# Power.net
KiCad netlist of a schematic drawn in Altium Designer
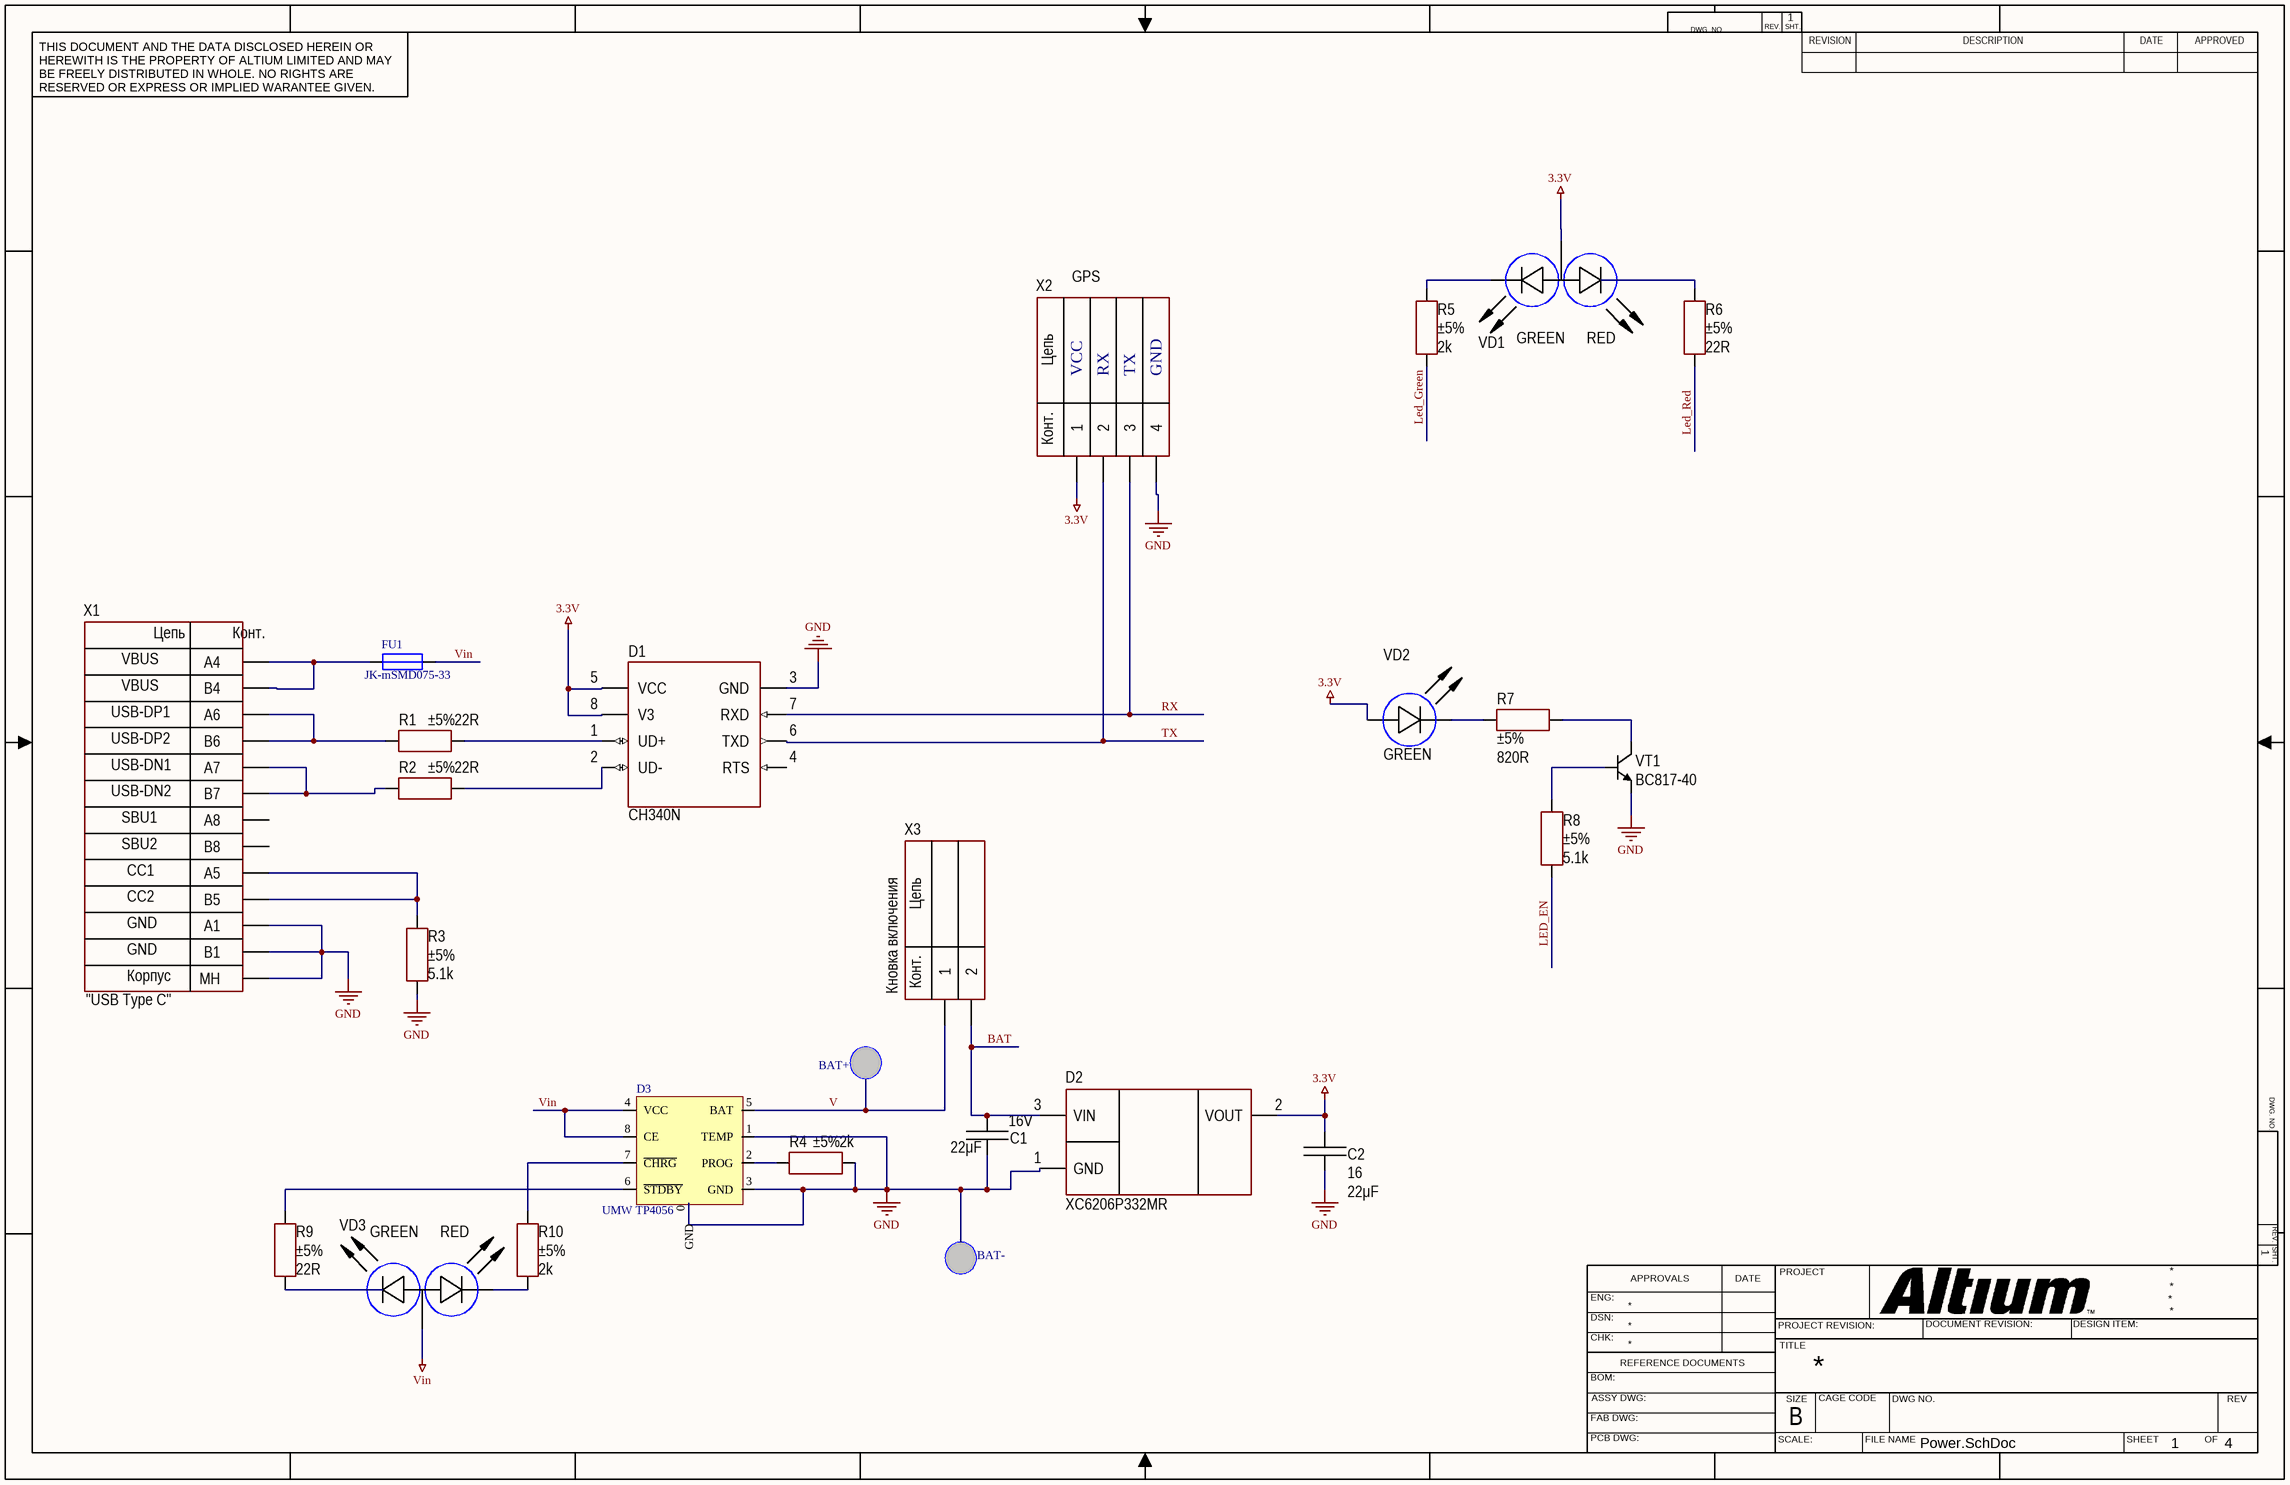
[diagram p0: Power.SchDoc]

(export (version "E")
  (design (tool "Eeschema 10.0.6"))
  (components
    (comp (ref "C1")
      (value "22μF")
      (footprint "standard-case:CAP: 1206")
      (fields
        (field (name "MANUFACTURER") "Yageo")
        (field (name "VALUEMANUFACTURERPARTNUMBER") "Ceramic capacitor, 22μF, X5R, ±20%, 16V, 1206, -55...+125°C")
        (field (name "TOLERANCE") "±20%")
        (field (name "VOLTAGE") "16V")
      )
      (libsource (lib "capacitor") (part "Ceramic_1206"))
    )
    (comp (ref "C2")
      (value "22μF")
      (footprint "standard-case:CAP: 1206")
      (fields
        (field (name "MANUFACTURER") "Yageo")
        (field (name "VALUEMANUFACTURERPARTNUMBER") "Ceramic capacitor, 22μF, X5R, ±20%, 16, 1206, -55...+125°C")
        (field (name "TOLERANCE") "±20%")
        (field (name "VOLTAGE") "16")
      )
      (libsource (lib "capacitor") (part "Ceramic_1206"))
    )
    (comp (ref "D1")
      (value "~")
      (footprint "8-SOIC")
      (description "USB-to-UART")
      (fields
        (field (name "MANUFACTURER") "WCH(Jiangsu Qin Heng)")
        (field (name "VALUEMANUFACTURERPARTNUMBER") "IC usb-to-uart bridge, USB2.0, 3...3.6V, -40...+85°C, 8- SOP")
        (field (name "PARTNUMBER") "CH340N")
      )
      (libsource (lib "ic-interface") (part "CH340N"))
    )
    (comp (ref "D2")
      (value "~")
      (footprint "SOT23")
      (description "Linear voltage regulator")
      (fields
        (field (name "MANUFACTURER") "Torex")
        (field (name "VALUEMANUFACTURERPARTNUMBER") "Linear voltage regulator, max input 6V, 0.25V, output 3.3V, 200mA, -40...+85°C, SOT-23")
        (field (name "PARTNUMBER") "XC6206P332MR")
      )
      (libsource (lib "ic-power-supply") (part "XC6206"))
    )
    (comp (ref "D3")
      (value "UMW TP4056")
      (footprint "SOP-8")
      (description "Микросхема TP4056-42-ESOP8")
      (libsource (lib "Geksan_my") (part "D TP4056-42-ESOP8"))
    )
    (comp (ref "FU1")
      (value "JK-mSMD075-33")
      (footprint "FUSE: 1812")
      (description "Предохраниетель ток срабатывания 1,5А, ток удержания 750мА")
      (libsource (lib "Fuse") (part "JK-mSMD075-33"))
    )
    (comp (ref "R1")
      (value "22R")
      (footprint "standard-case:RES: 0805")
      (fields
        (field (name "MANUFACTURER") "Yageo")
        (field (name "PARTNUMBER") "RC0805JR-0722RL")
        (field (name "VALUEMANUFACTURERPARTNUMBER") "Resistor film, 22R, ±5%, 0805, 0.125W, -55...+125°C")
        (field (name "TOLERANCE") "±5%")
      )
      (libsource (lib "") (part "Resistor_0805_1"))
    )
    (comp (ref "R2")
      (value "22R")
      (footprint "standard-case:RES: 0805")
      (fields
        (field (name "MANUFACTURER") "Yageo")
        (field (name "PARTNUMBER") "RC0805JR-0722RL")
        (field (name "VALUEMANUFACTURERPARTNUMBER") "Resistor film, 22R, ±5%, 0805, 0.125W, -55...+125°C")
        (field (name "TOLERANCE") "±5%")
      )
      (libsource (lib "") (part "Resistor_0805_1"))
    )
    (comp (ref "R3")
      (value "5.1k")
      (footprint "standard-case:RES: 0805")
      (fields
        (field (name "MANUFACTURER") "Yageo")
        (field (name "PARTNUMBER") "RC0805JR-075K1L")
        (field (name "VALUEMANUFACTURERPARTNUMBER") "Resistor film, 5.1k, ±5%, 0805, 0.125W, -55...+125°C")
        (field (name "TOLERANCE") "±5%")
      )
      (libsource (lib "resistor") (part "Resistor_0805"))
    )
    (comp (ref "R4")
      (value "2k")
      (footprint "standard-case:RES: 0805")
      (fields
        (field (name "MANUFACTURER") "Yageo")
        (field (name "PARTNUMBER") "RC0805JR-0712KL")
        (field (name "VALUEMANUFACTURERPARTNUMBER") "Resistor film, 2k, ±5%, 0805, 0.125W, -55...+125°C")
        (field (name "TOLERANCE") "±5%")
      )
      (libsource (lib "") (part "Resistor_0805_1"))
    )
    (comp (ref "R5")
      (value "2k")
      (footprint "standard-case:RES: 0805")
      (fields
        (field (name "MANUFACTURER") "Yageo")
        (field (name "PARTNUMBER") "RC0805JR-0712KL")
        (field (name "VALUEMANUFACTURERPARTNUMBER") "Resistor film, 2k, ±5%, 0805, 0.125W, -55...+125°C")
        (field (name "TOLERANCE") "±5%")
      )
      (libsource (lib "") (part "Resistor_0805_2"))
    )
    (comp (ref "R6")
      (value "22R")
      (footprint "standard-case:RES: 0805")
      (fields
        (field (name "MANUFACTURER") "Yageo")
        (field (name "PARTNUMBER") "RC0805JR-0722RL")
        (field (name "VALUEMANUFACTURERPARTNUMBER") "Resistor film, 22R, ±5%, 0805, 0.125W, -55...+125°C")
        (field (name "TOLERANCE") "±5%")
      )
      (libsource (lib "") (part "Resistor_0805_2"))
    )
    (comp (ref "R7")
      (value "820R")
      (footprint "standard-case:RES: 0805")
      (fields
        (field (name "MANUFACTURER") "Yageo")
        (field (name "PARTNUMBER") "RC0805JR-07820RL")
        (field (name "VALUEMANUFACTURERPARTNUMBER") "Resistor film, 820R, ±5%, 0805, 0.125W, -55...+125°C")
        (field (name "TOLERANCE") "±5%")
      )
      (libsource (lib "") (part "Resistor_0805_1"))
    )
    (comp (ref "R8")
      (value "5.1k")
      (footprint "standard-case:RES: 0805")
      (fields
        (field (name "MANUFACTURER") "Yageo")
        (field (name "PARTNUMBER") "RC0805JR-075K1L")
        (field (name "VALUEMANUFACTURERPARTNUMBER") "Resistor film, 5.1k, ±5%, 0805, 0.125W, -55...+125°C")
        (field (name "TOLERANCE") "±5%")
      )
      (libsource (lib "") (part "Resistor_0805_2"))
    )
    (comp (ref "R9")
      (value "22R")
      (footprint "standard-case:RES: 0805")
      (fields
        (field (name "MANUFACTURER") "Yageo")
        (field (name "PARTNUMBER") "RC0805JR-0722RL")
        (field (name "VALUEMANUFACTURERPARTNUMBER") "Resistor film, 22R, ±5%, 0805, 0.125W, -55...+125°C")
        (field (name "TOLERANCE") "±5%")
      )
      (libsource (lib "resistor") (part "Resistor_0805"))
    )
    (comp (ref "R10")
      (value "2k")
      (footprint "standard-case:RES: 0805")
      (fields
        (field (name "MANUFACTURER") "Yageo")
        (field (name "PARTNUMBER") "RC0805JR-0712KL")
        (field (name "VALUEMANUFACTURERPARTNUMBER") "Resistor film, 2k, ±5%, 0805, 0.125W, -55...+125°C")
        (field (name "TOLERANCE") "±5%")
      )
      (libsource (lib "resistor") (part "Resistor_0805"))
    )
    (comp (ref "VD1")
      (value "~")
      (footprint "DIODE: LED3MM_DUAL")
      (fields
        (field (name "VALUEMANUFACTURERPARTNUMBER") "LED, Green, *, *, 3mm, -55...+150°C")
        (field (name "COLOR") "GREEN      RED")
      )
      (libsource (lib "diode") (part "LED_DUAL_3mm"))
    )
    (comp (ref "VD2")
      (value "~")
      (footprint "DIODE: LED3MM_Y")
      (fields
        (field (name "VALUEMANUFACTURERPARTNUMBER") "LED, Green, *, *, *, -55...+150°C")
        (field (name "COLOR") "GREEN")
      )
      (libsource (lib "diode") (part "LED_single_3mm"))
    )
    (comp (ref "VD3")
      (value "~")
      (footprint "DIODE: LED3MM_DUAL")
      (fields
        (field (name "VALUEMANUFACTURERPARTNUMBER") "LED, Green, *, *, 3mm, -55...+150°C")
        (field (name "COLOR") "GREEN      RED")
      )
      (libsource (lib "diode") (part "LED_DUAL_3mm"))
    )
    (comp (ref "VT1")
      (value "~")
      (footprint "standard-case:SOT23")
      (fields
        (field (name "MANUFACTURER") "ON Semiconductor")
        (field (name "VALUEMANUFACTURERPARTNUMBER") "NPN transistor, 45V, 100mA, 100MHz, 250mW, 0.6V, 420, SOT-23, -55...+125°C")
        (field (name "PARTNUMBER") "ВС817-40")
      )
      (libsource (lib "transistor") (part "BJT_NPN_132"))
    )
    (comp (ref "X1")
      (value "~")
      (footprint "custom-case:CON: TYPE-C-31-M-12")
      (fields
        (field (name "MANUFACTURER") "Korean Hroparts")
        (field (name "VALUEMANUFACTURERPARTNUMBER") "USB Type C, 3A")
        (field (name "PARTNUMBER") "TYPE-C-31-M-12")
        (field (name "COMMENTTEXT") "\"USB Type C\"")
      )
      (libsource (lib "connector") (part "Connector_USB_Type_C"))
    )
    (comp (ref "X2")
      (value "~")
      (footprint "custom-case:CON: PLS-4")
      (fields
        (field (name "MANUFACTURER") "Connfly")
        (field (name "VALUEMANUFACTURERPARTNUMBER") "Connector, 4pin, 2.54mm, 500VAC, 3A")
        (field (name "PARTNUMBER") "PLS-4")
        (field (name "COMMENTTEXT") "GPS")
      )
      (libsource (lib "connector") (part "PLS-4"))
    )
    (comp (ref "X3")
      (value "~")
      (footprint "custom-case:CON: PLS-2")
      (fields
        (field (name "MANUFACTURER") "Connfly")
        (field (name "VALUEMANUFACTURERPARTNUMBER") "Connector, 2pin, 2.54mm, 500VAC, 3A")
        (field (name "PARTNUMBER") "PLS-2")
        (field (name "COMMENTTEXT") "Кновка включения")
      )
      (libsource (lib "connector") (part "PLS-2"))
    )
  )
  (nets
    (net (code "1") (name "/BAT") (class "Default")
      (node (ref "C1") (pin "2") (pinfunction "2_2") (pintype "passive"))
      (node (ref "D2") (pin "3") (pinfunction "VIN_3") (pintype "power_in"))
      (node (ref "X3") (pin "2") (pinfunction "2_2") (pintype "passive"))
    )
    (net (code "2") (name "/LED_EN") (class "Default")
      (node (ref "R8") (pin "2") (pinfunction "2_2") (pintype "passive"))
    )
    (net (code "3") (name "/Led_Green") (class "Default")
      (node (ref "R5") (pin "2") (pinfunction "2_2") (pintype "passive"))
    )
    (net (code "4") (name "/Led_Red") (class "Default")
      (node (ref "R6") (pin "2") (pinfunction "2_2") (pintype "passive"))
    )
    (net (code "5") (name "/RX") (class "Default")
      (node (ref "D1") (pin "7") (pinfunction "RXD_7") (pintype "input"))
      (node (ref "X2") (pin "3") (pinfunction "3_3") (pintype "power_in"))
    )
    (net (code "6") (name "/TX") (class "Default")
      (node (ref "D1") (pin "6") (pinfunction "TXD_6") (pintype "output"))
      (node (ref "X2") (pin "2") (pinfunction "2_2") (pintype "passive"))
    )
    (net (code "7") (name "/V") (class "Default")
      (node (ref "D3") (pin "5") (pinfunction "BAT_5") (pintype "open_collector"))
      (node (ref "X3") (pin "1") (pinfunction "1_1") (pintype "passive"))
    )
    (net (code "8") (name "3.3V") (class "Default")
      (node (ref "C2") (pin "2") (pinfunction "2_2") (pintype "passive"))
      (node (ref "D1") (pin "5") (pinfunction "VCC_5") (pintype "power_in"))
      (node (ref "D1") (pin "8") (pinfunction "V3_8") (pintype "passive"))
      (node (ref "D2") (pin "2") (pinfunction "VOUT_2") (pintype "power_in"))
      (node (ref "VD1") (pin "2") (pinfunction "A_2") (pintype "passive"))
      (node (ref "VD2") (pin "1") (pinfunction "A_1") (pintype "passive"))
      (node (ref "X2") (pin "1") (pinfunction "1_1") (pintype "passive"))
    )
    (net (code "9") (name "GND") (class "Default")
      (node (ref "C1") (pin "1") (pinfunction "1_1") (pintype "passive"))
      (node (ref "C2") (pin "1") (pinfunction "1_1") (pintype "passive"))
      (node (ref "D1") (pin "3") (pinfunction "GND_3") (pintype "power_in"))
      (node (ref "D2") (pin "1") (pinfunction "GND_1") (pintype "power_in"))
      (node (ref "D3") (pin "0") (pinfunction "GND_0") (pintype "power_in"))
      (node (ref "D3") (pin "1") (pinfunction "TEMP_1") (pintype "power_in"))
      (node (ref "D3") (pin "3") (pinfunction "GND_3") (pintype "power_in"))
      (node (ref "R3") (pin "1") (pinfunction "1_1") (pintype "passive"))
      (node (ref "R4") (pin "2") (pinfunction "2_2") (pintype "passive"))
      (node (ref "VT1") (pin "2") (pinfunction "E_2") (pintype "passive"))
      (node (ref "X1") (pin "A1") (pinfunction "A1_A1") (pintype "power_in"))
      (node (ref "X1") (pin "B1") (pinfunction "B1_B1") (pintype "power_in"))
      (node (ref "X1") (pin "MH") (pinfunction "MH_MH") (pintype "power_in"))
      (node (ref "X2") (pin "4") (pinfunction "4_4") (pintype "power_in"))
    )
    (net (code "10") (name "Net-(D1-UD+)") (class "Default")
      (node (ref "D1") (pin "1") (pinfunction "UD+_1") (pintype "bidirectional"))
      (node (ref "R1") (pin "2") (pinfunction "2_2") (pintype "passive"))
    )
    (net (code "11") (name "Net-(D1-UD-)") (class "Default")
      (node (ref "D1") (pin "2") (pinfunction "UD-_2") (pintype "bidirectional"))
      (node (ref "R2") (pin "2") (pinfunction "2_2") (pintype "passive"))
    )
    (net (code "12") (name "Net-(D3-PROG)") (class "Default")
      (node (ref "D3") (pin "2") (pinfunction "PROG_2") (pintype "power_in"))
      (node (ref "R4") (pin "1") (pinfunction "1_1") (pintype "passive"))
    )
    (net (code "13") (name "Net-(D3-~{CHRG})") (class "Default")
      (node (ref "D3") (pin "7") (pinfunction "~{CHRG}_7") (pintype "open_collector"))
      (node (ref "R10") (pin "2") (pinfunction "2_2") (pintype "passive"))
    )
    (net (code "14") (name "Net-(D3-~{STDBY})") (class "Default")
      (node (ref "D3") (pin "6") (pinfunction "~{STDBY}_6") (pintype "passive"))
      (node (ref "R9") (pin "2") (pinfunction "2_2") (pintype "passive"))
    )
    (net (code "15") (name "Net-(FU1-Pad1)") (class "Default")
      (node (ref "FU1") (pin "1") (pinfunction "1_1") (pintype "passive"))
      (node (ref "X1") (pin "A4") (pinfunction "A4_A4") (pintype "passive"))
      (node (ref "X1") (pin "B4") (pinfunction "B4_B4") (pintype "passive"))
    )
    (net (code "16") (name "Net-(R1-Pad1)") (class "Default")
      (node (ref "R1") (pin "1") (pinfunction "1_1") (pintype "passive"))
      (node (ref "X1") (pin "A6") (pinfunction "A6_A6") (pintype "power_in"))
      (node (ref "X1") (pin "B6") (pinfunction "B6_B6") (pintype "power_in"))
    )
    (net (code "17") (name "Net-(R2-Pad1)") (class "Default")
      (node (ref "R2") (pin "1") (pinfunction "1_1") (pintype "passive"))
      (node (ref "X1") (pin "A7") (pinfunction "A7_A7") (pintype "power_in"))
      (node (ref "X1") (pin "B7") (pinfunction "B7_B7") (pintype "power_in"))
    )
    (net (code "18") (name "Net-(R3-Pad2)") (class "Default")
      (node (ref "R3") (pin "2") (pinfunction "2_2") (pintype "passive"))
      (node (ref "X1") (pin "A5") (pinfunction "A5_A5") (pintype "power_in"))
      (node (ref "X1") (pin "B5") (pinfunction "B5_B5") (pintype "power_in"))
    )
    (net (code "19") (name "Net-(R5-Pad1)") (class "Default")
      (node (ref "R5") (pin "1") (pinfunction "1_1") (pintype "passive"))
      (node (ref "VD1") (pin "3") (pinfunction "C_3") (pintype "passive"))
    )
    (net (code "20") (name "Net-(R6-Pad1)") (class "Default")
      (node (ref "R6") (pin "1") (pinfunction "1_1") (pintype "passive"))
      (node (ref "VD1") (pin "1") (pinfunction "C_1") (pintype "passive"))
    )
    (net (code "21") (name "Net-(R9-Pad1)") (class "Default")
      (node (ref "R9") (pin "1") (pinfunction "1_1") (pintype "passive"))
      (node (ref "VD3") (pin "1") (pinfunction "C_1") (pintype "passive"))
    )
    (net (code "22") (name "Net-(R10-Pad1)") (class "Default")
      (node (ref "R10") (pin "1") (pinfunction "1_1") (pintype "passive"))
      (node (ref "VD3") (pin "3") (pinfunction "C_3") (pintype "passive"))
    )
    (net (code "23") (name "Net-(VD2-C)") (class "Default")
      (node (ref "R7") (pin "1") (pinfunction "1_1") (pintype "passive"))
      (node (ref "VD2") (pin "2") (pinfunction "C_2") (pintype "passive"))
    )
    (net (code "24") (name "Net-(VT1-B)") (class "Default")
      (node (ref "R8") (pin "1") (pinfunction "1_1") (pintype "passive"))
      (node (ref "VT1") (pin "1") (pinfunction "B_1") (pintype "passive"))
    )
    (net (code "25") (name "Net-(VT1-C)") (class "Default")
      (node (ref "R7") (pin "2") (pinfunction "2_2") (pintype "passive"))
      (node (ref "VT1") (pin "3") (pinfunction "C_3") (pintype "passive"))
    )
    (net (code "26") (name "Vin") (class "Default")
      (node (ref "D3") (pin "4") (pinfunction "VCC_4") (pintype "open_collector"))
      (node (ref "D3") (pin "8") (pinfunction "CE_8") (pintype "passive"))
      (node (ref "FU1") (pin "2") (pinfunction "2_2") (pintype "passive"))
      (node (ref "VD3") (pin "2") (pinfunction "A_2") (pintype "passive"))
    )
    (net (code "27") (name "unconnected-(D1-RTS-Pad4)") (class "Default")
      (node (ref "D1") (pin "4") (pinfunction "RTS_4") (pintype "input"))
    )
    (net (code "28") (name "unconnected-(X1-PadA8)") (class "Default")
      (node (ref "X1") (pin "A8") (pinfunction "A8_A8") (pintype "power_in"))
    )
    (net (code "29") (name "unconnected-(X1-PadB8)") (class "Default")
      (node (ref "X1") (pin "B8") (pinfunction "B8_B8") (pintype "power_in"))
    )
  )
)
